# 3_Relay_Implausibility.net
KiCad netlist of a schematic drawn in Altium Designer
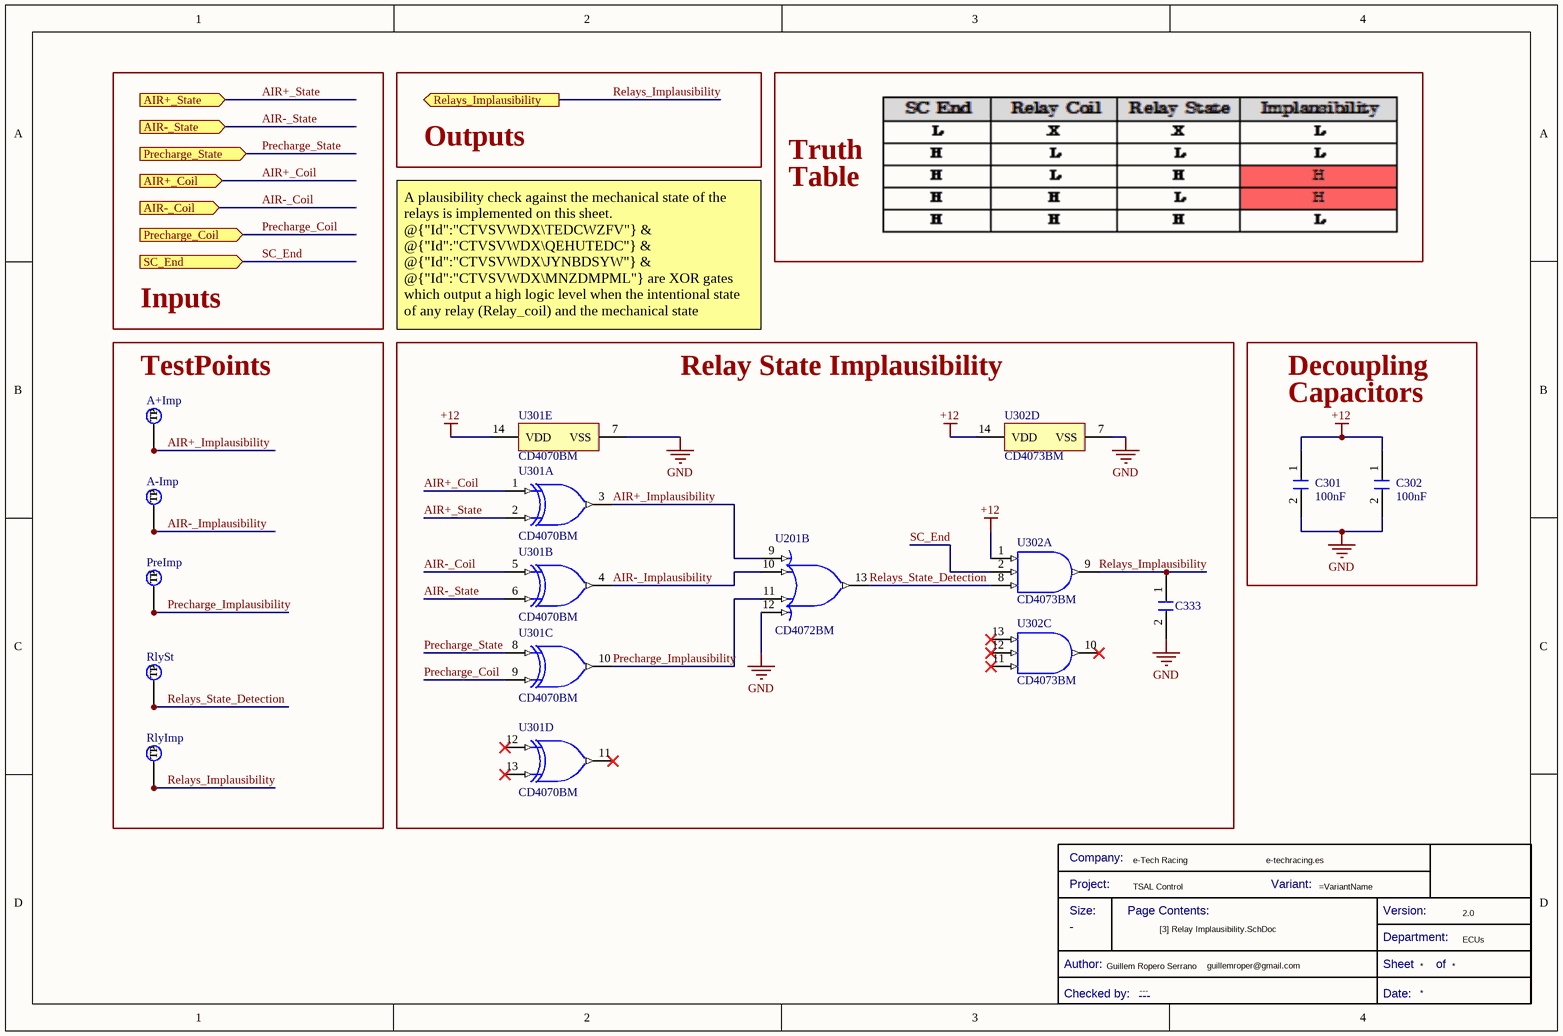
[diagram p0: [3] Relay Implausibility.SchDoc]

(export (version "E")
  (design (tool "Eeschema 10.0.6"))
  (components
    (comp (ref "A+Imp")
      (value "TestPoint")
      (footprint "TestPoint")
      (description "Test Point 1x1 mm")
      (fields (field (name ".SCHCHECK") "GP") (field (name ".CREATOR") "GP") (field (name ".PCBCHECK") "GP"))
      (libsource (lib "EMEA- E-Tech Racing- I'Escola d'Enginyeria de Barcelona Est") (part "TestPoint"))
    )
    (comp (ref "A-Imp")
      (value "TestPoint")
      (footprint "TestPoint")
      (description "Test Point 1x1 mm")
      (fields (field (name ".SCHCHECK") "GP") (field (name ".CREATOR") "GP") (field (name ".PCBCHECK") "GP"))
      (libsource (lib "EMEA- E-Tech Racing- I'Escola d'Enginyeria de Barcelona Est") (part "TestPoint"))
    )
    (comp (ref "C301")
      (value "100nF")
      (footprint "C0805FNPC-R")
      (description "Cap, 0.1ΜF, 50V, 10%, X7R, 0805")
      (fields
        (field (name "TOLERANCE") "10%")
        (field (name "Comment") "C100n-50V-0805FNPC-X7R")
        (field (name ".CREATOR") "DR")
      )
      (libsource (lib "EMEA- E-Tech Racing- I'Escola d'Enginyeria de Barcelona Est") (part "C100p-50V-0805FNPC-C0G/NP0"))
    )
    (comp (ref "C302")
      (value "100nF")
      (footprint "C0805FNPC-R")
      (description "Cap, 0.1ΜF, 50V, 10%, X7R, 0805")
      (fields
        (field (name "TOLERANCE") "10%")
        (field (name "Comment") "C100n-50V-0805FNPC-X7R")
        (field (name ".CREATOR") "DR")
      )
      (libsource (lib "EMEA- E-Tech Racing- I'Escola d'Enginyeria de Barcelona Est") (part "C100p-50V-0805FNPC-C0G/NP0"))
    )
    (comp (ref "C333")
      (value "C15p-50V-0805FNPC-NP0")
      (footprint "C0805FNPC-R")
      (description "Cap, 15PF, 50V, 5%, C0G/NP0, 0805")
      (fields (field (name "TOLERANCE") "5%") (field (name ".CREATOR") "DR"))
      (libsource (lib "EMEA- E-Tech Racing- I'Escola d'Enginyeria de Barcelona Est") (part "C100p-50V-0805FNPC-C0G/NP0"))
    )
    (comp (ref "PreImp")
      (value "TestPoint")
      (footprint "TestPoint")
      (description "Test Point 1x1 mm")
      (fields (field (name ".SCHCHECK") "GP") (field (name ".CREATOR") "GP") (field (name ".PCBCHECK") "GP"))
      (libsource (lib "EMEA- E-Tech Racing- I'Escola d'Enginyeria de Barcelona Est") (part "TestPoint"))
    )
    (comp (ref "RlyImp")
      (value "TestPoint")
      (footprint "TestPoint")
      (description "Test Point 1x1 mm")
      (fields (field (name ".SCHCHECK") "GP") (field (name ".CREATOR") "GP") (field (name ".PCBCHECK") "GP"))
      (libsource (lib "EMEA- E-Tech Racing- I'Escola d'Enginyeria de Barcelona Est") (part "TestPoint"))
    )
    (comp (ref "RlySt")
      (value "TestPoint")
      (footprint "TestPoint")
      (description "Test Point 1x1 mm")
      (fields (field (name ".SCHCHECK") "GP") (field (name ".CREATOR") "GP") (field (name ".PCBCHECK") "GP"))
      (libsource (lib "EMEA- E-Tech Racing- I'Escola d'Enginyeria de Barcelona Est") (part "TestPoint"))
    )
    (comp (ref "U201")
      (value "CD4072BM")
      (footprint "D0014A_N")
      (description "OR Gate, 4000/14000/40000 Series, 2-Func, 4-Input, CMOS, PDSO14")
      (libsource (lib "EMEA- E-Tech Racing- I'Escola d'Enginyeria de Barcelona Est") (part "TI-CD4072B-14"))
    )
    (comp (ref "U301")
      (value "CD4070BM")
      (footprint "D0014A_N")
      (description "XOR Gate, 4000/14000/40000 Series, 4-Func, 2-Input, CMOS, PDSO14")
      (libsource (lib "EMEA- E-Tech Racing- I'Escola d'Enginyeria de Barcelona Est") (part "TI-XOR-4-2IN-14_A"))
    )
    (comp (ref "U302")
      (value "CD4073BM")
      (footprint "D0014A_N")
      (description "AND Gate, 4000/14000/40000 Series, 3-Func, 3-Input, CMOS, PDSO14")
      (libsource (lib "EMEA- E-Tech Racing- I'Escola d'Enginyeria de Barcelona Est") (part "TI-CD4073B-14"))
    )
  )
  (nets
    (net (code "1") (name "+12") (class "Default")
      (node (ref "C301") (pin "1") (pinfunction "1_1") (pintype "passive"))
      (node (ref "C302") (pin "1") (pinfunction "1_1") (pintype "passive"))
      (node (ref "U301") (pin "14") (pinfunction "VDD_14") (pintype "power_in"))
      (node (ref "U302") (pin "1") (pinfunction "A_1") (pintype "input"))
      (node (ref "U302") (pin "14") (pinfunction "VDD_14") (pintype "power_in"))
    )
    (net (code "2") (name "/AIR+_Coil") (class "Default")
      (node (ref "U301") (pin "1") (pinfunction "A_1") (pintype "input"))
    )
    (net (code "3") (name "/AIR+_Implausibility") (class "Default")
      (node (ref "A+Imp") (pin "1") (pinfunction "TP_1") (pintype "passive"))
      (node (ref "U201") (pin "9") (pinfunction "E_9") (pintype "input"))
      (node (ref "U301") (pin "3") (pinfunction "J_3") (pintype "output"))
    )
    (net (code "4") (name "/AIR+_State") (class "Default")
      (node (ref "U301") (pin "2") (pinfunction "B_2") (pintype "input"))
    )
    (net (code "5") (name "/AIR-_Coil") (class "Default")
      (node (ref "U301") (pin "5") (pinfunction "C_5") (pintype "input"))
    )
    (net (code "6") (name "/AIR-_Implausibility") (class "Default")
      (node (ref "A-Imp") (pin "1") (pinfunction "TP_1") (pintype "passive"))
      (node (ref "U201") (pin "10") (pinfunction "F_10") (pintype "input"))
      (node (ref "U301") (pin "4") (pinfunction "K_4") (pintype "output"))
    )
    (net (code "7") (name "/AIR-_State") (class "Default")
      (node (ref "U301") (pin "6") (pinfunction "D_6") (pintype "input"))
    )
    (net (code "8") (name "/Precharge_Coil") (class "Default")
      (node (ref "U301") (pin "9") (pinfunction "F_9") (pintype "input"))
    )
    (net (code "9") (name "/Precharge_Implausibility") (class "Default")
      (node (ref "PreImp") (pin "1") (pinfunction "TP_1") (pintype "passive"))
      (node (ref "U201") (pin "11") (pinfunction "G_11") (pintype "input"))
      (node (ref "U301") (pin "10") (pinfunction "L_10") (pintype "output"))
    )
    (net (code "10") (name "/Precharge_State") (class "Default")
      (node (ref "U301") (pin "8") (pinfunction "E_8") (pintype "input"))
    )
    (net (code "11") (name "/Relays_Implausibility") (class "Default")
      (node (ref "C333") (pin "1") (pinfunction "1_1") (pintype "passive"))
      (node (ref "RlyImp") (pin "1") (pinfunction "TP_1") (pintype "passive"))
      (node (ref "U302") (pin "9") (pinfunction "J_9") (pintype "output"))
    )
    (net (code "12") (name "/Relays_State_Detection") (class "Default")
      (node (ref "RlySt") (pin "1") (pinfunction "TP_1") (pintype "passive"))
      (node (ref "U201") (pin "13") (pinfunction "K_13") (pintype "output"))
      (node (ref "U302") (pin "8") (pinfunction "C_8") (pintype "input"))
    )
    (net (code "13") (name "/SC_End") (class "Default")
      (node (ref "U302") (pin "2") (pinfunction "B_2") (pintype "input"))
    )
    (net (code "14") (name "GND") (class "Default")
      (node (ref "C301") (pin "2") (pinfunction "2_2") (pintype "passive"))
      (node (ref "C302") (pin "2") (pinfunction "2_2") (pintype "passive"))
      (node (ref "C333") (pin "2") (pinfunction "2_2") (pintype "passive"))
      (node (ref "U201") (pin "12") (pinfunction "H_12") (pintype "input"))
      (node (ref "U301") (pin "7") (pinfunction "VSS_7") (pintype "power_in"))
      (node (ref "U302") (pin "7") (pinfunction "VSS_7") (pintype "power_in"))
    )
    (net (code "15") (name "unconnected-(U301D-G-Pad12)") (class "Default")
      (node (ref "U301") (pin "12") (pinfunction "G_12") (pintype "input+no_connect"))
    )
    (net (code "16") (name "unconnected-(U301D-H-Pad13)") (class "Default")
      (node (ref "U301") (pin "13") (pinfunction "H_13") (pintype "input+no_connect"))
    )
    (net (code "17") (name "unconnected-(U301D-M-Pad11)") (class "Default")
      (node (ref "U301") (pin "11") (pinfunction "M_11") (pintype "output+no_connect"))
    )
    (net (code "18") (name "unconnected-(U302C-G-Pad13)") (class "Default")
      (node (ref "U302") (pin "13") (pinfunction "G_13") (pintype "input+no_connect"))
    )
    (net (code "19") (name "unconnected-(U302C-H-Pad12)") (class "Default")
      (node (ref "U302") (pin "12") (pinfunction "H_12") (pintype "input+no_connect"))
    )
    (net (code "20") (name "unconnected-(U302C-I-Pad11)") (class "Default")
      (node (ref "U302") (pin "11") (pinfunction "I_11") (pintype "input+no_connect"))
    )
    (net (code "21") (name "unconnected-(U302C-L-Pad10)") (class "Default")
      (node (ref "U302") (pin "10") (pinfunction "L_10") (pintype "output+no_connect"))
    )
  )
)
